# Power_Mananget.net
KiCad netlist of a schematic drawn in Altium Designer
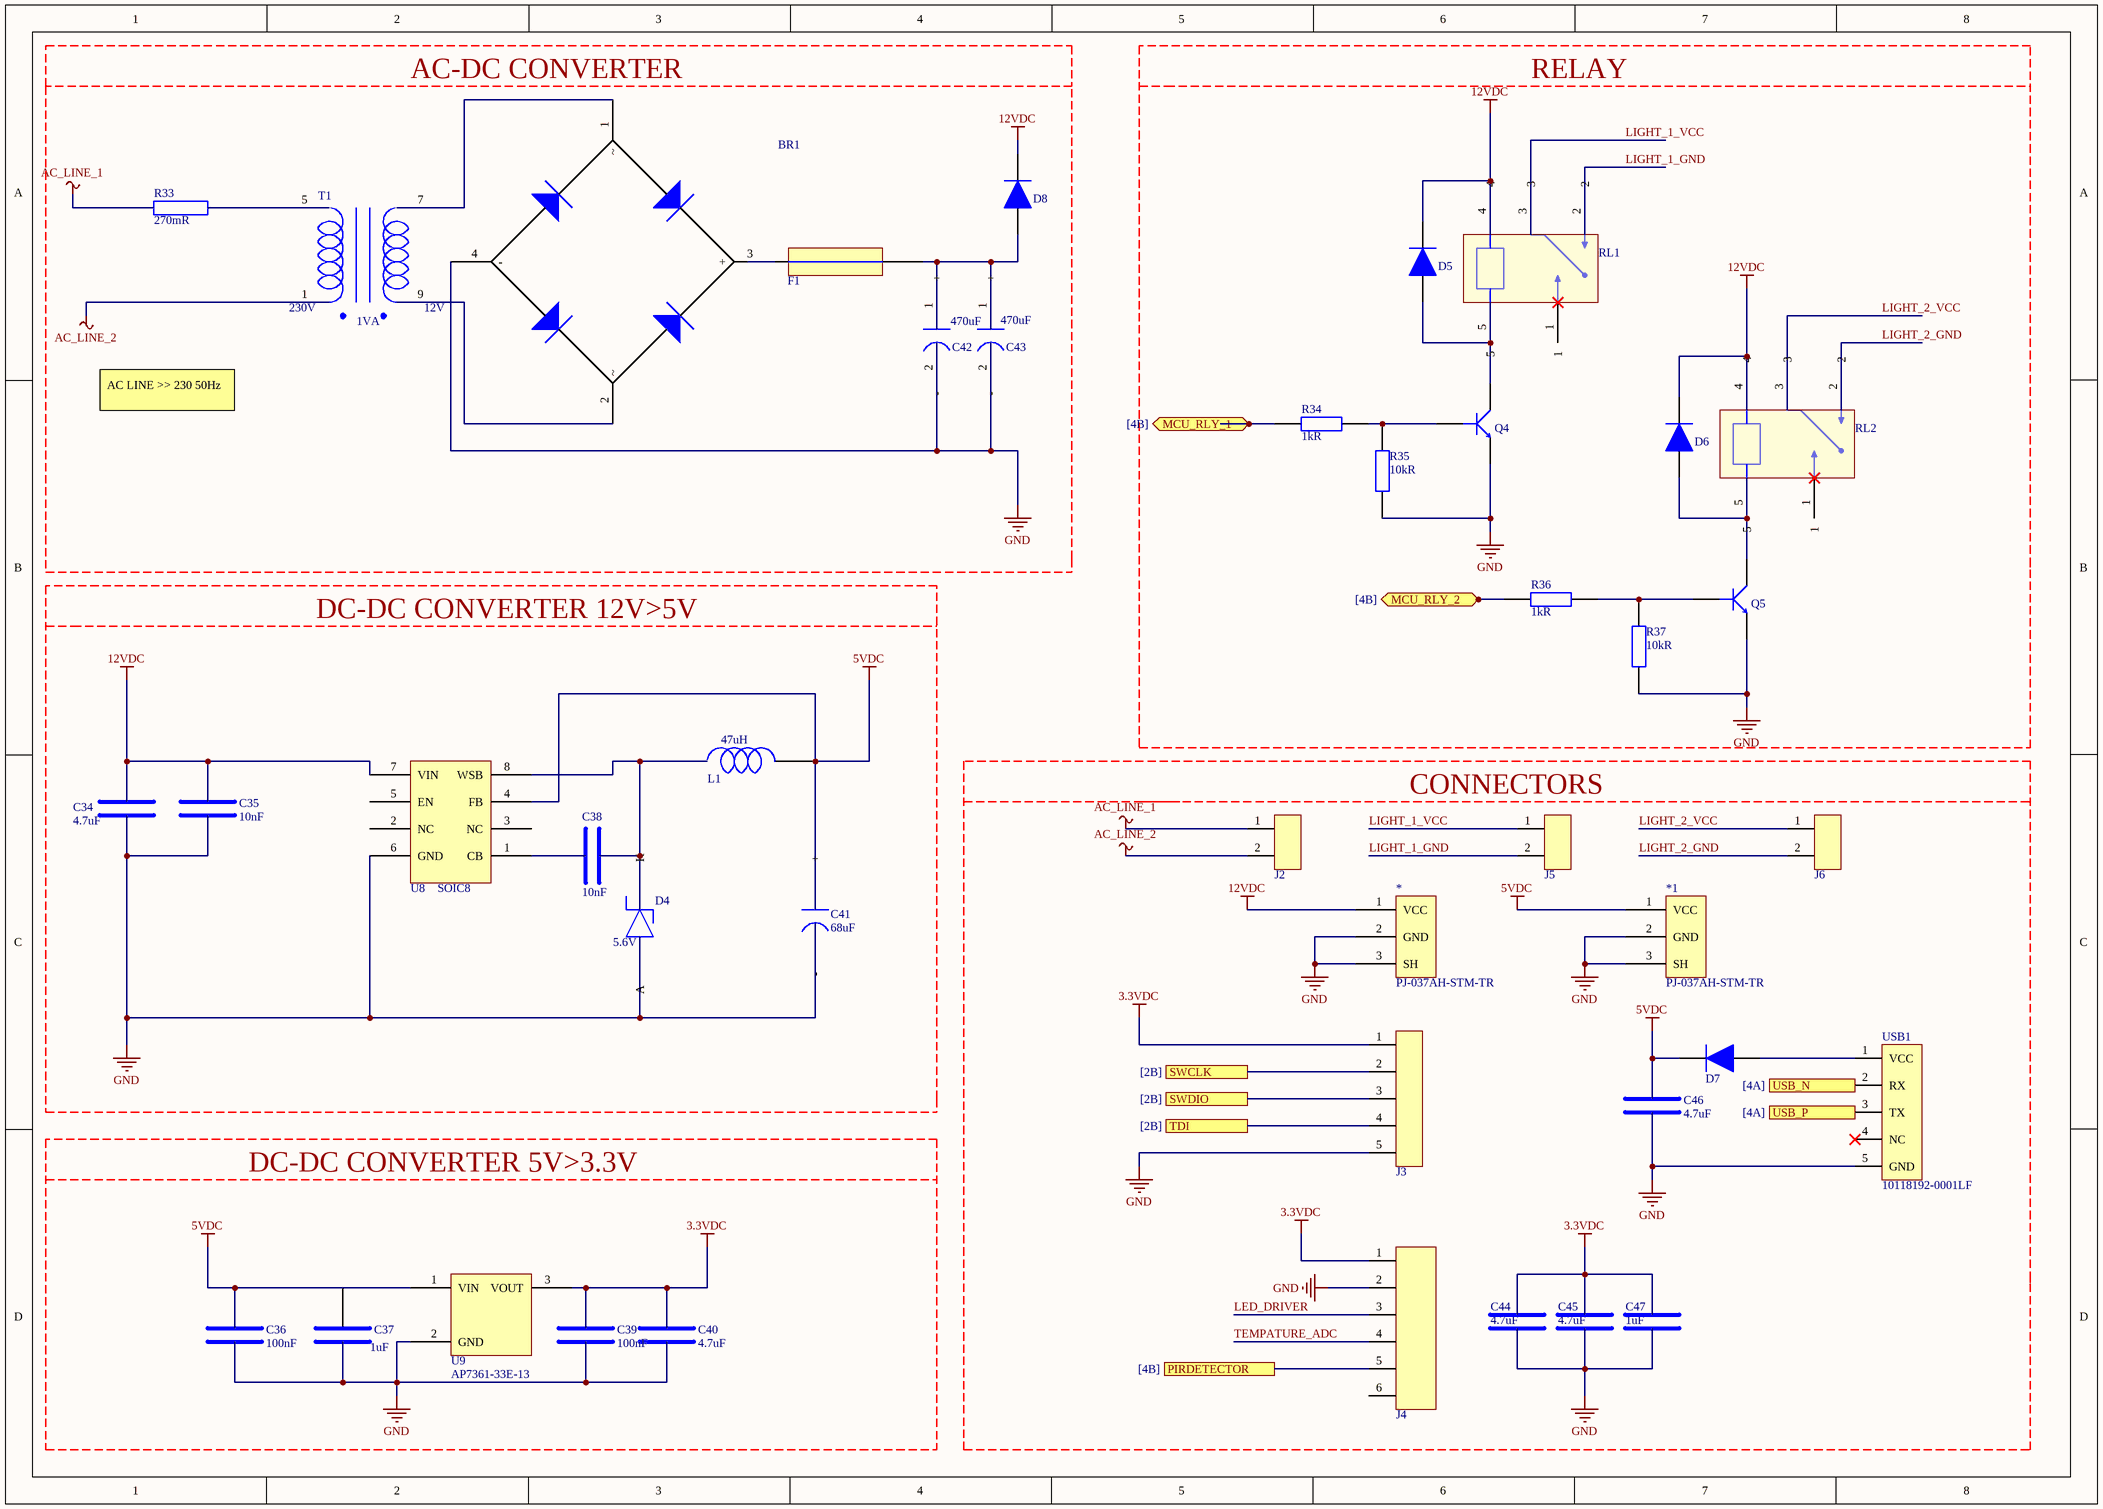
[diagram p0: Power Mananget.SchDoc]

(export (version "E")
  (design (tool "Eeschema 10.0.6"))
  (components
    (comp (ref "*")
      (value "PJ-037AH-STM-TR")
      (footprint "JACK")
      (libsource (lib "Integrated_Library1") (part "PJ-037AH-STM-TR"))
    )
    (comp (ref "*1")
      (value "PJ-037AH-STM-TR")
      (footprint "JACK")
      (libsource (lib "Integrated_Library1") (part "PJ-037AH-STM-TR"))
    )
    (comp (ref "BR1")
      (value "DB105S")
      (footprint "DB105S")
      (description "Bridge Rectifier Single Phase Standard 600 V Surface Mount DB-S")
      (fields (field (name "DESIGNED BY") "SİSA"))
      (libsource (lib "Integrated_Library1") (part "DB105S"))
    )
    (comp (ref "C34")
      (value "4.7uF")
      (footprint "CAP_0805")
      (fields
        (field (name "MANUFACTURER") "Samsung")
        (field (name "MANUFACTURER PART NUMBER") "CL21A475KAQNNNE")
      )
      (libsource (lib "Integrated_Library1") (part "CAP CER 4.7uF 0805"))
    )
    (comp (ref "C35")
      (value "10nF")
      (footprint "CAP_0603")
      (fields
        (field (name "MANUFACTURER") "Walsin Technologies")
        (field (name "MANUFACTURER PART NUMBER") "0603B103K160CT")
      )
      (libsource (lib "Integrated_Library1") (part "CAP CER 10000PF"))
    )
    (comp (ref "C36")
      (value "100nF")
      (footprint "CAP_0805")
      (fields
        (field (name "MANUFACTURER") "Samsung")
        (field (name "MANUFACTURER PART NUMBER") "CL21B104KBCNNNC")
        (field (name "Comment") "CAP CER 0.1uF 0805")
      )
      (libsource (lib "Integrated_Library1") (part "CAP CER 0.1uF 0805"))
    )
    (comp (ref "C37")
      (value "1uF")
      (footprint "CAP_0805")
      (fields
        (field (name "MANUFACTURER") "Samsung")
        (field (name "MANUFACTURER PART NUMBER") "CL21B105KBFNNNE")
      )
      (libsource (lib "Integrated_Library1") (part "CAP CER 1uF"))
    )
    (comp (ref "C38")
      (value "10nF")
      (footprint "CAP_0603")
      (fields
        (field (name "MANUFACTURER") "Walsin Technologies")
        (field (name "MANUFACTURER PART NUMBER") "0603B103K160CT")
      )
      (libsource (lib "Integrated_Library1") (part "CAP CER 10000PF"))
    )
    (comp (ref "C39")
      (value "100nF")
      (footprint "CAP_0805")
      (fields
        (field (name "MANUFACTURER") "Samsung")
        (field (name "MANUFACTURER PART NUMBER") "CL21B104KBCNNNC")
        (field (name "Comment") "CAP CER 0.1uF 0805")
      )
      (libsource (lib "Integrated_Library1") (part "CAP CER 0.1uF 0805"))
    )
    (comp (ref "C40")
      (value "4.7uF")
      (footprint "CAP_0805")
      (fields
        (field (name "MANUFACTURER") "Samsung")
        (field (name "MANUFACTURER PART NUMBER") "CL21A475KAQNNNE")
      )
      (libsource (lib "Integrated_Library1") (part "CAP CER 4.7uF 0805"))
    )
    (comp (ref "C41")
      (value "68uF")
      (footprint "CAP_EEV")
      (fields
        (field (name "MANUFACTURER") "KEMET")
        (field (name "MANUFACTURER PART NUMBER") "EEV686M035A9HAA")
      )
      (libsource (lib "Integrated_Library1") (part "CAP ALU 68uF"))
    )
    (comp (ref "C42")
      (value "470uF")
      (footprint "ESH477M050AH4AA")
      (fields
        (field (name "MANUFACTURER") "KEMET")
        (field (name "MANUFACTURER PART NUMBER") "ESH477M050AH4AA")
      )
      (libsource (lib "Integrated_Library1") (part "ESH477M050AH4AA"))
    )
    (comp (ref "C43")
      (value "470uF")
      (footprint "ESH477M050AH4AA")
      (fields
        (field (name "MANUFACTURER") "KEMET")
        (field (name "MANUFACTURER PART NUMBER") "ESH477M050AH4AA")
      )
      (libsource (lib "Integrated_Library1") (part "ESH477M050AH4AA"))
    )
    (comp (ref "C44")
      (value "4.7uF")
      (footprint "CAP_0805")
      (fields
        (field (name "MANUFACTURER") "Samsung")
        (field (name "MANUFACTURER PART NUMBER") "CL21A475KAQNNNE")
      )
      (libsource (lib "Integrated_Library1") (part "CAP CER 4.7uF 0805"))
    )
    (comp (ref "C45")
      (value "4.7uF")
      (footprint "CAP_0805")
      (fields
        (field (name "MANUFACTURER") "Samsung")
        (field (name "MANUFACTURER PART NUMBER") "CL21A475KAQNNNE")
      )
      (libsource (lib "Integrated_Library1") (part "CAP CER 4.7uF 0805"))
    )
    (comp (ref "C46")
      (value "4.7uF")
      (footprint "CAP_0805")
      (fields
        (field (name "MANUFACTURER") "Samsung")
        (field (name "MANUFACTURER PART NUMBER") "CL21A475KAQNNNE")
      )
      (libsource (lib "Integrated_Library1") (part "CAP CER 4.7uF 0805"))
    )
    (comp (ref "C47")
      (value "1uF")
      (footprint "CAP_0805")
      (fields
        (field (name "MANUFACTURER") "Samsung")
        (field (name "MANUFACTURER PART NUMBER") "CL21B105KBFNNNE")
      )
      (libsource (lib "Integrated_Library1") (part "CAP CER 1uF"))
    )
    (comp (ref "D4")
      (value "1SMB5919BT3G")
      (footprint "SMB")
      (description "Zener Diode, 5.6V V(Z), 5%, 0.55W, Silicon, Unidirectional, DO-214AA")
      (fields (field (name "MANUFACTURER") "onsemi") (field (name "REFERENCE VOLTAGE-NOM") "5.6V"))
      (libsource (lib "Integrated_Library1") (part "DIODE ZENER 5.6V 3W SMB"))
    )
    (comp (ref "D5")
      (value "1N4148WS")
      (footprint "SOD323F")
      (description "Diode, Single, 75 V, 150 mA, 1 V, 4 ns")
      (fields (field (name "MANUFACTURER") "ON Semiconductor / Fairchild"))
      (libsource (lib "Integrated_Library1") (part "1N4148WS"))
    )
    (comp (ref "D6")
      (value "1N4148WS")
      (footprint "SOD323F")
      (description "Diode, Single, 75 V, 150 mA, 1 V, 4 ns")
      (fields (field (name "MANUFACTURER") "ON Semiconductor / Fairchild"))
      (libsource (lib "Integrated_Library1") (part "1N4148WS"))
    )
    (comp (ref "D7")
      (value "1N4148WS")
      (footprint "SOD323F")
      (description "Diode, Single, 75 V, 150 mA, 1 V, 4 ns")
      (fields (field (name "MANUFACTURER") "ON Semiconductor / Fairchild"))
      (libsource (lib "Integrated_Library1") (part "1N4148WS"))
    )
    (comp (ref "D8")
      (value "1N4148WS")
      (footprint "SOD323F")
      (description "Diode, Single, 75 V, 150 mA, 1 V, 4 ns")
      (fields (field (name "MANUFACTURER") "ON Semiconductor / Fairchild"))
      (libsource (lib "Integrated_Library1") (part "1N4148WS"))
    )
    (comp (ref "F1")
      (value "3413.0216.22")
      (footprint "3413.0216.22")
      (description "Electric Fuse, Very Fast Blow, 1A, 32VAC, 63VDC, 63A (IR), Surface Mount, 1206")
      (fields (field (name "MANUFACTURER") "Schurter"))
      (libsource (lib "Integrated_Library1") (part "3413.0216.22"))
    )
    (comp (ref "J2")
      (value "TBP01R1-508-02BE")
      (footprint "TBP01R1-508")
      (description "Conn Shrouded Header HDR 2 POS 5.08mm Solder RA Side Entry Thru-Hole Bag")
      (fields (field (name "MANUFACTURER") "CUI"))
      (libsource (lib "Integrated_Library1") (part "TBP01R1-508-02BE"))
    )
    (comp (ref "J3")
      (value "SMH-105-02-L-S")
      (footprint "PINHEADER1X5_RA")
      (description ".100 C.L. HORIZONTAL SMT SOCKET")
      (fields (field (name "MANUFACTURER") "Samtec"))
      (libsource (lib "Integrated_Library1") (part "SMH-105-02-L-S"))
    )
    (comp (ref "J4")
      (value "64800611622")
      (footprint "64800611622")
      (description "1.50mm 6PIN Connector")
      (fields (field (name "MANUFACTURER") "Wurth Electronics"))
      (libsource (lib "Integrated_Library1") (part "64800611622_conn_6pin"))
    )
    (comp (ref "J5")
      (value "TBP01R1-508-02BE")
      (footprint "TBP01R1-508")
      (description "Conn Shrouded Header HDR 2 POS 5.08mm Solder RA Side Entry Thru-Hole Bag")
      (fields (field (name "MANUFACTURER") "CUI"))
      (libsource (lib "Integrated_Library1") (part "TBP01R1-508-02BE"))
    )
    (comp (ref "J6")
      (value "TBP01R1-508-02BE")
      (footprint "TBP01R1-508")
      (description "Conn Shrouded Header HDR 2 POS 5.08mm Solder RA Side Entry Thru-Hole Bag")
      (fields (field (name "MANUFACTURER") "CUI"))
      (libsource (lib "Integrated_Library1") (part "TBP01R1-508-02BE"))
    )
    (comp (ref "L1")
      (value "78438335470")
      (footprint "IND_1212")
      (description "General Purpose Inductor, 47uH, 20%, 1 Element, Iron Alloy-Core, SMD, 1212")
      (fields (field (name "MANUFACTURER") "Wurth Electronics"))
      (libsource (lib "Integrated_Library1") (part "FIXED IND 47UH 390MA 2.3 OHM SMD"))
    )
    (comp (ref "Q4")
      (value "MMBT3904-7-F")
      (footprint "SOT-23F")
      (description "Transistor General Purpose BJT NPN 40 Volt 0.2A Automotive 3-Pin SOT-23")
      (fields (field (name "MANUFACTURER") "Diodes Zetex"))
      (libsource (lib "Integrated_Library1") (part "MMBT3904-7-F"))
    )
    (comp (ref "Q5")
      (value "MMBT3904-7-F")
      (footprint "SOT-23F")
      (description "Transistor General Purpose BJT NPN 40 Volt 0.2A Automotive 3-Pin SOT-23")
      (fields (field (name "MANUFACTURER") "Diodes Zetex"))
      (libsource (lib "Integrated_Library1") (part "MMBT3904-7-F"))
    )
    (comp (ref "R33")
      (value "270mR")
      (footprint "RES_AXIAL_W")
      (description "Fixed Resistor, Wire Wound, 5W, 0.27ohm, 200V, 5% +/-Tol, 300ppm/Cel, 8738")
      (fields
        (field (name "MANUFACTURER") "NTE Electronics")
        (field (name "MANUFACTURER PART NUMBER") "5WD27")
      )
      (libsource (lib "Integrated_Library1") (part "5WD27"))
    )
    (comp (ref "R34")
      (value "RC0603FR-0710KL")
      (footprint "RES_0603 - duplicate")
      (description "RES 1K %1 OHM 0603 SMD")
      (fields
        (field (name "MANUFACTURER") "Yageo")
        (field (name "MANUFACTURER PART NUMBER") "RC0603JR-071KL")
        (field (name "RESISTANCE") "1kR")
        (field (name "DESIGNED BY") "BERK")
      )
      (libsource (lib "Integrated_Library1") (part "RES 1K OHM 0603"))
    )
    (comp (ref "R35")
      (value "RC0603FR-0710KL")
      (footprint "RES_0603 - duplicate")
      (description "RES 10K %1 OHM 0603 SMD")
      (fields
        (field (name "MANUFACTURER") "Yageo")
        (field (name "TOLERANCE") "1%")
        (field (name "RESISTANCE") "10kR")
        (field (name "DESIGNED BY") "BERK")
      )
      (libsource (lib "Integrated_Library1") (part "RES 10K OHM 0603"))
    )
    (comp (ref "R36")
      (value "RC0603FR-0710KL")
      (footprint "RES_0603 - duplicate")
      (description "RES 1K %1 OHM 0603 SMD")
      (fields
        (field (name "MANUFACTURER") "Yageo")
        (field (name "MANUFACTURER PART NUMBER") "RC0603JR-071KL")
        (field (name "RESISTANCE") "1kR")
        (field (name "DESIGNED BY") "BERK")
      )
      (libsource (lib "Integrated_Library1") (part "RES 1K OHM 0603"))
    )
    (comp (ref "R37")
      (value "RC0603FR-0710KL")
      (footprint "RES_0603 - duplicate")
      (description "RES 10K %1 OHM 0603 SMD")
      (fields
        (field (name "MANUFACTURER") "Yageo")
        (field (name "TOLERANCE") "1%")
        (field (name "RESISTANCE") "10kR")
        (field (name "DESIGNED BY") "BERK")
      )
      (libsource (lib "Integrated_Library1") (part "RES 10K OHM 0603"))
    )
    (comp (ref "RL1")
      (value "ALQ-112")
      (footprint "ALQ-112")
      (fields (field (name "MANUFACTURER") "Panasonic") (field (name "MANUFACTURER PART NUMBER") "ALQ112"))
      (libsource (lib "Integrated_Library1") (part "ALQ-112"))
    )
    (comp (ref "RL2")
      (value "ALQ-112")
      (footprint "ALQ-112")
      (fields (field (name "MANUFACTURER") "Panasonic") (field (name "MANUFACTURER PART NUMBER") "ALQ112"))
      (libsource (lib "Integrated_Library1") (part "ALQ-112"))
    )
    (comp (ref "T1")
      (value "BV302S12010")
      (footprint "BV302S12010")
      (description "Split Bobbin Power Transformer, 1VA, 230V-12V")
      (fields
        (field (name "MANUFACTURER") "Zettler Magnetics")
        (field (name "SECONDARY") "12V")
        (field (name "PRİMARY") "230V")
        (field (name "RATED POWER") "1VA")
        (field (name "DESIGNED BY") "SiSA")
      )
      (libsource (lib "Integrated_Library1") (part "BV302S12010"))
    )
    (comp (ref "U8")
      (value "LM2675MX-12/NOPB")
      (footprint "SOIC8")
      (description "Switching Regulator, Voltage-mode, 2.2A, 275kHz Switching Freq-Max, DMOS, PDSO8")
      (fields
        (field (name "MANUFACTURER") "TI National Semiconductor")
        (field (name "CASE/PACKAGE") "SOIC8")
        (field (name "DESIGNED BY") "SisA")
      )
      (libsource (lib "Integrated_Library1") (part "LM2675MX-12/NOPB"))
    )
    (comp (ref "U9")
      (value "AP7361-33E-13")
      (footprint "AP7361-33E-13")
      (description "Fixed Positive LDO Regulator, 3.3V, 0.7V Dropout, CMOS, PSSO3")
      (fields (field (name "MANUFACTURER") "Diodes"))
      (libsource (lib "Integrated_Library1") (part "AP7361-33E-13"))
    )
    (comp (ref "USB1")
      (value "10118192-0001LF")
      (footprint "MICRO_B_USB")
      (description "CONN RCPT USB2.0 MICRO B SMD R/A")
      (fields (field (name "MANUFACTURER") "Amphenol FCI") (field (name "DESIGNED BY") "BERK"))
      (libsource (lib "Integrated_Library1") (part "Micro B USB Connector"))
    )
  )
  (nets
    (net (code "1") (name "/LED_DRIVER") (class "Default") (node (ref "J4") (pin "3") (pintype "power_in")))
    (net (code "2") (name "/LIGHT_1_GND") (class "Default")
      (node (ref "J5") (pin "2") (pinfunction "2_2") (pintype "power_in"))
      (node (ref "RL1") (pin "2") (pinfunction "2_2") (pintype "passive"))
    )
    (net (code "3") (name "/LIGHT_1_VCC") (class "Default")
      (node (ref "J5") (pin "1") (pinfunction "1_1") (pintype "power_in"))
      (node (ref "RL1") (pin "3") (pinfunction "3_3") (pintype "passive"))
    )
    (net (code "4") (name "/LIGHT_2_GND") (class "Default")
      (node (ref "J6") (pin "2") (pinfunction "2_2") (pintype "power_in"))
      (node (ref "RL2") (pin "2") (pinfunction "2_2") (pintype "passive"))
    )
    (net (code "5") (name "/LIGHT_2_VCC") (class "Default")
      (node (ref "J6") (pin "1") (pinfunction "1_1") (pintype "power_in"))
      (node (ref "RL2") (pin "3") (pinfunction "3_3") (pintype "passive"))
    )
    (net (code "6") (name "/MCU_RLY_1") (class "Default")
      (node (ref "R34") (pin "1") (pinfunction "1_1") (pintype "passive"))
    )
    (net (code "7") (name "/MCU_RLY_2") (class "Default")
      (node (ref "R36") (pin "1") (pinfunction "1_1") (pintype "passive"))
    )
    (net (code "8") (name "/PIRDETECTOR") (class "Default") (node (ref "J4") (pin "5") (pintype "power_in")))
    (net (code "9") (name "/SWCLK") (class "Default")
      (node (ref "J3") (pin "2") (pinfunction "2_2") (pintype "power_in"))
    )
    (net (code "10") (name "/SWDIO") (class "Default")
      (node (ref "J3") (pin "3") (pinfunction "3_3") (pintype "power_in"))
    )
    (net (code "11") (name "/TDI") (class "Default")
      (node (ref "J3") (pin "4") (pinfunction "4_4") (pintype "power_in"))
    )
    (net (code "12") (name "/TEMPATURE_ADC") (class "Default")
      (node (ref "J4") (pin "4") (pintype "power_in"))
    )
    (net (code "13") (name "/USB_N") (class "Default")
      (node (ref "USB1") (pin "2") (pinfunction "RX_2") (pintype "power_in"))
    )
    (net (code "14") (name "/USB_P") (class "Default")
      (node (ref "USB1") (pin "3") (pinfunction "TX_3") (pintype "power_in"))
    )
    (net (code "15") (name "3.3VDC") (class "Default")
      (node (ref "C39") (pin "1") (pinfunction "1_1") (pintype "passive"))
      (node (ref "C40") (pin "1") (pinfunction "1_1") (pintype "passive"))
      (node (ref "C44") (pin "1") (pinfunction "1_1") (pintype "passive"))
      (node (ref "C45") (pin "1") (pinfunction "1_1") (pintype "passive"))
      (node (ref "C47") (pin "1") (pinfunction "1_1") (pintype "passive"))
      (node (ref "J3") (pin "1") (pinfunction "1_1") (pintype "power_in"))
      (node (ref "J4") (pin "1") (pintype "power_in"))
      (node (ref "U9") (pin "3") (pinfunction "VOUT_3") (pintype "passive"))
    )
    (net (code "16") (name "5VDC") (class "Default")
      (node (ref "*1") (pin "1") (pinfunction "VCC_1") (pintype "power_in"))
      (node (ref "C36") (pin "1") (pinfunction "1_1") (pintype "passive"))
      (node (ref "C41") (pin "2") (pinfunction "+_2") (pintype "passive"))
      (node (ref "C46") (pin "1") (pinfunction "1_1") (pintype "passive"))
      (node (ref "D7") (pin "1") (pinfunction "1_1") (pintype "power_in"))
      (node (ref "L1") (pin "2") (pinfunction "7_2") (pintype "passive"))
      (node (ref "U8") (pin "4") (pinfunction "FB_4") (pintype "passive"))
      (node (ref "U9") (pin "1") (pinfunction "VIN_1") (pintype "passive"))
    )
    (net (code "17") (name "12VDC") (class "Default")
      (node (ref "*") (pin "1") (pinfunction "VCC_1") (pintype "power_in"))
      (node (ref "C34") (pin "1") (pinfunction "1_1") (pintype "passive"))
      (node (ref "C35") (pin "1") (pinfunction "1_1") (pintype "passive"))
      (node (ref "D5") (pin "1") (pinfunction "1_1") (pintype "power_in"))
      (node (ref "D6") (pin "1") (pinfunction "1_1") (pintype "power_in"))
      (node (ref "D8") (pin "1") (pinfunction "1_1") (pintype "power_in"))
      (node (ref "RL1") (pin "4") (pinfunction "4_4") (pintype "passive"))
      (node (ref "RL2") (pin "4") (pinfunction "4_4") (pintype "passive"))
      (node (ref "U8") (pin "7") (pinfunction "VIN_7") (pintype "passive"))
    )
    (net (code "18") (name "AC_LINE_1") (class "Default")
      (node (ref "J2") (pin "1") (pinfunction "1_1") (pintype "power_in"))
      (node (ref "R33") (pin "1") (pinfunction "11_1") (pintype "passive"))
    )
    (net (code "19") (name "AC_LINE_2") (class "Default")
      (node (ref "J2") (pin "2") (pinfunction "2_2") (pintype "power_in"))
      (node (ref "T1") (pin "1") (pinfunction "10_1") (pintype "passive"))
    )
    (net (code "20") (name "GND") (class "Default")
      (node (ref "*") (pin "2") (pinfunction "GND_2") (pintype "power_in"))
      (node (ref "*") (pin "3") (pinfunction "SH_3") (pintype "passive"))
      (node (ref "*1") (pin "2") (pinfunction "GND_2") (pintype "power_in"))
      (node (ref "*1") (pin "3") (pinfunction "SH_3") (pintype "passive"))
      (node (ref "BR1") (pin "4") (pinfunction "-_4") (pintype "passive"))
      (node (ref "C34") (pin "2") (pinfunction "2_2") (pintype "passive"))
      (node (ref "C35") (pin "2") (pinfunction "2_2") (pintype "passive"))
      (node (ref "C36") (pin "2") (pinfunction "2_2") (pintype "passive"))
      (node (ref "C37") (pin "2") (pinfunction "2_2") (pintype "passive"))
      (node (ref "C39") (pin "2") (pinfunction "2_2") (pintype "passive"))
      (node (ref "C40") (pin "2") (pinfunction "2_2") (pintype "passive"))
      (node (ref "C41") (pin "1") (pinfunction "-_1") (pintype "passive"))
      (node (ref "C42") (pin "2") (pinfunction "-_2") (pintype "passive"))
      (node (ref "C43") (pin "2") (pinfunction "-_2") (pintype "passive"))
      (node (ref "C44") (pin "2") (pinfunction "2_2") (pintype "passive"))
      (node (ref "C45") (pin "2") (pinfunction "2_2") (pintype "passive"))
      (node (ref "C46") (pin "2") (pinfunction "2_2") (pintype "passive"))
      (node (ref "C47") (pin "2") (pinfunction "2_2") (pintype "passive"))
      (node (ref "D4") (pin "2") (pinfunction "A_2") (pintype "passive"))
      (node (ref "J3") (pin "5") (pinfunction "5_5") (pintype "power_in"))
      (node (ref "J4") (pin "2") (pintype "power_in"))
      (node (ref "Q4") (pin "2") (pinfunction "E_2") (pintype "power_in"))
      (node (ref "Q5") (pin "2") (pinfunction "E_2") (pintype "power_in"))
      (node (ref "R35") (pin "1") (pinfunction "1_1") (pintype "passive"))
      (node (ref "R37") (pin "1") (pinfunction "1_1") (pintype "passive"))
      (node (ref "U8") (pin "6") (pinfunction "GND_6") (pintype "passive"))
      (node (ref "U9") (pin "2") (pinfunction "GND_2") (pintype "passive"))
      (node (ref "USB1") (pin "5") (pinfunction "GND_5") (pintype "power_in"))
    )
    (net (code "21") (name "Net-(BR1-+)") (class "Default")
      (node (ref "BR1") (pin "3") (pinfunction "+_3") (pintype "passive"))
      (node (ref "F1") (pin "1") (pintype "passive"))
    )
    (net (code "22") (name "Net-(C42-+)") (class "Default")
      (node (ref "C42") (pin "1") (pinfunction "+_1") (pintype "passive"))
      (node (ref "C43") (pin "1") (pinfunction "+_1") (pintype "passive"))
      (node (ref "D8") (pin "2") (pinfunction "2_2") (pintype "power_in"))
      (node (ref "F1") (pin "2") (pintype "passive"))
    )
    (net (code "23") (name "Net-(D4-K)") (class "Default")
      (node (ref "C38") (pin "2") (pinfunction "2_2") (pintype "passive"))
      (node (ref "D4") (pin "1") (pinfunction "K_1") (pintype "passive"))
      (node (ref "L1") (pin "1") (pinfunction "6_1") (pintype "passive"))
      (node (ref "U8") (pin "8") (pinfunction "WSB_8") (pintype "passive"))
    )
    (net (code "24") (name "Net-(Q4-B)") (class "Default")
      (node (ref "Q4") (pin "1") (pinfunction "B_1") (pintype "power_in"))
      (node (ref "R34") (pin "2") (pinfunction "2_2") (pintype "passive"))
      (node (ref "R35") (pin "2") (pinfunction "2_2") (pintype "passive"))
    )
    (net (code "25") (name "Net-(Q4-C)") (class "Default")
      (node (ref "D5") (pin "2") (pinfunction "2_2") (pintype "power_in"))
      (node (ref "Q4") (pin "3") (pinfunction "C_3") (pintype "power_in"))
      (node (ref "RL1") (pin "5") (pinfunction "5_5") (pintype "passive"))
    )
    (net (code "26") (name "Net-(Q5-B)") (class "Default")
      (node (ref "Q5") (pin "1") (pinfunction "B_1") (pintype "power_in"))
      (node (ref "R36") (pin "2") (pinfunction "2_2") (pintype "passive"))
      (node (ref "R37") (pin "2") (pinfunction "2_2") (pintype "passive"))
    )
    (net (code "27") (name "Net-(Q5-C)") (class "Default")
      (node (ref "D6") (pin "2") (pinfunction "2_2") (pintype "power_in"))
      (node (ref "Q5") (pin "3") (pinfunction "C_3") (pintype "power_in"))
      (node (ref "RL2") (pin "5") (pinfunction "5_5") (pintype "passive"))
    )
    (net (code "28") (name "Net-(R33-10)") (class "Default")
      (node (ref "R33") (pin "2") (pinfunction "10_2") (pintype "passive"))
      (node (ref "T1") (pin "5") (pinfunction "11_5") (pintype "passive"))
    )
    (net (code "29") (name "Net-(T1-12)") (class "Default")
      (node (ref "BR1") (pin "1") (pinfunction "~_1") (pintype "passive"))
      (node (ref "T1") (pin "7") (pinfunction "12_7") (pintype "passive"))
    )
    (net (code "30") (name "Net-(T1-13)") (class "Default")
      (node (ref "BR1") (pin "2") (pinfunction "~_2") (pintype "passive"))
      (node (ref "T1") (pin "9") (pinfunction "13_9") (pintype "passive"))
    )
    (net (code "31") (name "Net-(U8-CB)") (class "Default")
      (node (ref "C38") (pin "1") (pinfunction "1_1") (pintype "passive"))
      (node (ref "U8") (pin "1") (pinfunction "CB_1") (pintype "passive"))
    )
    (net (code "32") (name "Net-(USB1-VCC)") (class "Default")
      (node (ref "D7") (pin "2") (pinfunction "2_2") (pintype "power_in"))
      (node (ref "USB1") (pin "1") (pinfunction "VCC_1") (pintype "power_in"))
    )
    (net (code "33") (name "unconnected-(C37-Pad1)") (class "Default")
      (node (ref "C37") (pin "1") (pinfunction "1_1") (pintype "passive"))
    )
    (net (code "34") (name "unconnected-(J4-Pad6)") (class "Default")
      (node (ref "J4") (pin "6") (pintype "power_in"))
    )
    (net (code "35") (name "unconnected-(RL1-Pad1)") (class "Default")
      (node (ref "RL1") (pin "1") (pinfunction "1_1") (pintype "passive+no_connect"))
    )
    (net (code "36") (name "unconnected-(RL2-Pad1)") (class "Default")
      (node (ref "RL2") (pin "1") (pinfunction "1_1") (pintype "passive+no_connect"))
    )
    (net (code "37") (name "unconnected-(U8-EN-Pad5)") (class "Default")
      (node (ref "U8") (pin "5") (pinfunction "EN_5") (pintype "passive"))
    )
    (net (code "38") (name "unconnected-(U8-NC-Pad2)") (class "Default")
      (node (ref "U8") (pin "2") (pinfunction "NC_2") (pintype "passive"))
    )
    (net (code "39") (name "unconnected-(U8-NC-Pad3)") (class "Default")
      (node (ref "U8") (pin "3") (pinfunction "NC_3") (pintype "passive"))
    )
    (net (code "40") (name "unconnected-(USB1-NC-Pad4)") (class "Default")
      (node (ref "USB1") (pin "4") (pinfunction "NC_4") (pintype "power_in+no_connect"))
    )
  )
)
